# power_supply.net
KiCad netlist of a schematic drawn in EAGLE
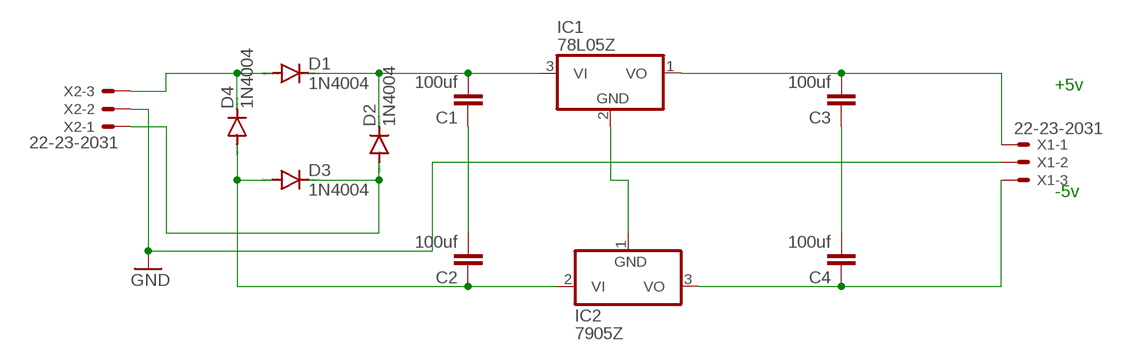
[diagram p0: schematic, sheet 1]

(export (version "E")
  (design (tool "Eeschema 10.0.6"))
  (components
    (comp (ref "C1")
      (value "100uf")
      (footprint "eagle-import:C2.5-3")
      (libsource (lib "eagle-import") (part "C2,5-3"))
    )
    (comp (ref "C2")
      (value "100uf")
      (footprint "eagle-import:C2.5-3")
      (libsource (lib "eagle-import") (part "C2,5-3"))
    )
    (comp (ref "C3")
      (value "100uf")
      (footprint "eagle-import:C2.5-3")
      (libsource (lib "eagle-import") (part "C2,5-3"))
    )
    (comp (ref "C4")
      (value "100uf")
      (footprint "eagle-import:C2.5-3")
      (libsource (lib "eagle-import") (part "C2,5-3"))
    )
    (comp (ref "D1")
      (value "1N4004")
      (footprint "eagle-import:DO41-10")
      (libsource (lib "eagle-import") (part "1N4004"))
    )
    (comp (ref "D2")
      (value "1N4004")
      (footprint "eagle-import:DO41-10")
      (libsource (lib "eagle-import") (part "1N4004"))
    )
    (comp (ref "D3")
      (value "1N4004")
      (footprint "eagle-import:DO41-10")
      (libsource (lib "eagle-import") (part "1N4004"))
    )
    (comp (ref "D4")
      (value "1N4004")
      (footprint "eagle-import:DO41-10")
      (libsource (lib "eagle-import") (part "1N4004"))
    )
    (comp (ref "IC1")
      (value "78L05Z")
      (footprint "eagle-import:TO92")
      (libsource (lib "eagle-import") (part "78ZL05"))
    )
    (comp (ref "IC2")
      (value "7905Z")
      (footprint "eagle-import:TO92")
      (libsource (lib "eagle-import") (part "79ZL05"))
    )
    (comp (ref "X1")
      (value "22-23-2031")
      (footprint "eagle-import:22-23-2031")
      (fields (field (name "MF") "MOLEX"))
      (libsource (lib "eagle-import") (part "22-23-2031"))
    )
    (comp (ref "X2")
      (value "22-23-2031")
      (footprint "eagle-import:22-23-2031")
      (fields (field (name "MF") "MOLEX"))
      (libsource (lib "eagle-import") (part "22-23-2031"))
    )
  )
  (nets
    (net (code "1") (name "GND") (class "Default")
      (node (ref "X1") (pin "2") (pinfunction "S_2") (pintype "passive"))
      (node (ref "X2") (pin "2") (pinfunction "S_2") (pintype "passive"))
    )
    (net (code "2") (name "Net-(C1-Pad1)") (class "Default")
      (node (ref "C1") (pin "1") (pinfunction "1_1") (pintype "passive"))
      (node (ref "C2") (pin "2") (pinfunction "2_2") (pintype "passive"))
    )
    (net (code "3") (name "Net-(C3-Pad1)") (class "Default")
      (node (ref "C3") (pin "1") (pinfunction "1_1") (pintype "passive"))
      (node (ref "C4") (pin "2") (pinfunction "2_2") (pintype "passive"))
    )
    (net (code "4") (name "Net-(IC1-GND)") (class "Default")
      (node (ref "IC1") (pin "2") (pinfunction "GND_2") (pintype "passive"))
      (node (ref "IC2") (pin "1") (pinfunction "GND_1") (pintype "passive"))
    )
    (net (code "5") (name "Net-(IC1-VI)") (class "Default")
      (node (ref "C1") (pin "2") (pinfunction "2_2") (pintype "passive"))
      (node (ref "D1") (pin "C") (pinfunction "C_C") (pintype "passive"))
      (node (ref "D2") (pin "C") (pinfunction "C_C") (pintype "passive"))
      (node (ref "IC1") (pin "3") (pinfunction "VI_3") (pintype "input"))
    )
    (net (code "6") (name "Net-(IC1-VO)") (class "Default")
      (node (ref "C3") (pin "2") (pinfunction "2_2") (pintype "passive"))
      (node (ref "IC1") (pin "1") (pinfunction "VO_1") (pintype "passive"))
      (node (ref "X1") (pin "1") (pinfunction "S_1") (pintype "passive"))
    )
    (net (code "7") (name "Net-(IC2-VI)") (class "Default")
      (node (ref "C2") (pin "1") (pinfunction "1_1") (pintype "passive"))
      (node (ref "D3") (pin "A") (pinfunction "A_A") (pintype "passive"))
      (node (ref "D4") (pin "A") (pinfunction "A_A") (pintype "passive"))
      (node (ref "IC2") (pin "2") (pinfunction "VI_2") (pintype "input"))
    )
    (net (code "8") (name "Net-(IC2-VO)") (class "Default")
      (node (ref "C4") (pin "1") (pinfunction "1_1") (pintype "passive"))
      (node (ref "IC2") (pin "3") (pinfunction "VO_3") (pintype "passive"))
      (node (ref "X1") (pin "3") (pinfunction "S_3") (pintype "passive"))
    )
    (net (code "9") (name "Net-(X2A-S)") (class "Default")
      (node (ref "D2") (pin "A") (pinfunction "A_A") (pintype "passive"))
      (node (ref "D3") (pin "C") (pinfunction "C_C") (pintype "passive"))
      (node (ref "X2") (pin "1") (pinfunction "S_1") (pintype "passive"))
    )
    (net (code "10") (name "Net-(X2C-S)") (class "Default")
      (node (ref "D1") (pin "A") (pinfunction "A_A") (pintype "passive"))
      (node (ref "D4") (pin "C") (pinfunction "C_C") (pintype "passive"))
      (node (ref "X2") (pin "3") (pinfunction "S_3") (pintype "passive"))
    )
  )
)
